# ovc3868-2.net
KiCad netlist of a schematic drawn in EAGLE
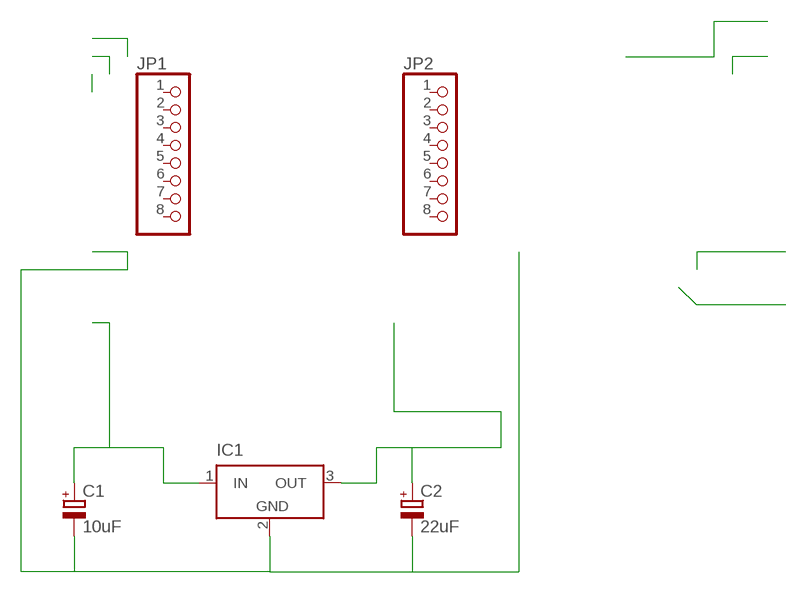
[diagram p0: schematic, sheet 1]

(export (version "E")
  (design (tool "Eeschema 10.0.6"))
  (components
    (comp (ref "C1")
      (value "10uF")
      (footprint "eagle-import:140CLH-0810")
      (libsource (lib "eagle-import") (part "CPOL-EU140CLH-0810"))
    )
    (comp (ref "C2")
      (value "22uF")
      (footprint "eagle-import:140CLH-0810")
      (libsource (lib "eagle-import") (part "CPOL-EU140CLH-0810"))
    )
    (comp (ref "IC1")
      (value "LT1129CST5")
      (footprint "eagle-import:SOT223")
      (fields (field (name "MPN") "LT1129CST-5#PBF"))
      (libsource (lib "eagle-import") (part "LT1129CST5"))
    )
    (comp (ref "JP1")
      (value "PINHD-1X8")
      (footprint "eagle-import:1X08")
      (libsource (lib "eagle-import") (part "PINHD-1X8"))
    )
    (comp (ref "JP2")
      (value "PINHD-1X8")
      (footprint "eagle-import:1X08")
      (libsource (lib "eagle-import") (part "PINHD-1X8"))
    )
  )
  (nets
    (net (code "1") (name "Net-(IC1A-GND)") (class "Default")
      (node (ref "C1") (pin "-") (pinfunction "-_-") (pintype "passive"))
      (node (ref "C2") (pin "-") (pinfunction "-_-") (pintype "passive"))
      (node (ref "IC1") (pin "2") (pinfunction "GND_2") (pintype "power_in"))
    )
    (net (code "2") (name "Net-(IC1A-IN)") (class "Default")
      (node (ref "C1") (pin "+") (pinfunction "+_+") (pintype "passive"))
      (node (ref "IC1") (pin "1") (pinfunction "IN_1") (pintype "input"))
    )
    (net (code "3") (name "Net-(IC1A-OUT)") (class "Default")
      (node (ref "C2") (pin "+") (pinfunction "+_+") (pintype "passive"))
      (node (ref "IC1") (pin "3") (pinfunction "OUT_3") (pintype "output"))
    )
    (net (code "4") (name "unconnected-(JP1-Pad1)") (class "Default")
      (node (ref "JP1") (pin "1") (pinfunction "1_1") (pintype "passive"))
    )
    (net (code "5") (name "unconnected-(JP1-Pad2)") (class "Default")
      (node (ref "JP1") (pin "2") (pinfunction "2_2") (pintype "passive"))
    )
    (net (code "6") (name "unconnected-(JP1-Pad3)") (class "Default")
      (node (ref "JP1") (pin "3") (pinfunction "3_3") (pintype "passive"))
    )
    (net (code "7") (name "unconnected-(JP1-Pad4)") (class "Default")
      (node (ref "JP1") (pin "4") (pinfunction "4_4") (pintype "passive"))
    )
    (net (code "8") (name "unconnected-(JP1-Pad5)") (class "Default")
      (node (ref "JP1") (pin "5") (pinfunction "5_5") (pintype "passive"))
    )
    (net (code "9") (name "unconnected-(JP1-Pad6)") (class "Default")
      (node (ref "JP1") (pin "6") (pinfunction "6_6") (pintype "passive"))
    )
    (net (code "10") (name "unconnected-(JP1-Pad7)") (class "Default")
      (node (ref "JP1") (pin "7") (pinfunction "7_7") (pintype "passive"))
    )
    (net (code "11") (name "unconnected-(JP1-Pad8)") (class "Default")
      (node (ref "JP1") (pin "8") (pinfunction "8_8") (pintype "passive"))
    )
    (net (code "12") (name "unconnected-(JP2-Pad1)") (class "Default")
      (node (ref "JP2") (pin "1") (pinfunction "1_1") (pintype "passive"))
    )
    (net (code "13") (name "unconnected-(JP2-Pad2)") (class "Default")
      (node (ref "JP2") (pin "2") (pinfunction "2_2") (pintype "passive"))
    )
    (net (code "14") (name "unconnected-(JP2-Pad3)") (class "Default")
      (node (ref "JP2") (pin "3") (pinfunction "3_3") (pintype "passive"))
    )
    (net (code "15") (name "unconnected-(JP2-Pad4)") (class "Default")
      (node (ref "JP2") (pin "4") (pinfunction "4_4") (pintype "passive"))
    )
    (net (code "16") (name "unconnected-(JP2-Pad5)") (class "Default")
      (node (ref "JP2") (pin "5") (pinfunction "5_5") (pintype "passive"))
    )
    (net (code "17") (name "unconnected-(JP2-Pad6)") (class "Default")
      (node (ref "JP2") (pin "6") (pinfunction "6_6") (pintype "passive"))
    )
    (net (code "18") (name "unconnected-(JP2-Pad7)") (class "Default")
      (node (ref "JP2") (pin "7") (pinfunction "7_7") (pintype "passive"))
    )
    (net (code "19") (name "unconnected-(JP2-Pad8)") (class "Default")
      (node (ref "JP2") (pin "8") (pinfunction "8_8") (pintype "passive"))
    )
  )
)
